# untitled.net
KiCad netlist of a schematic drawn in EAGLE
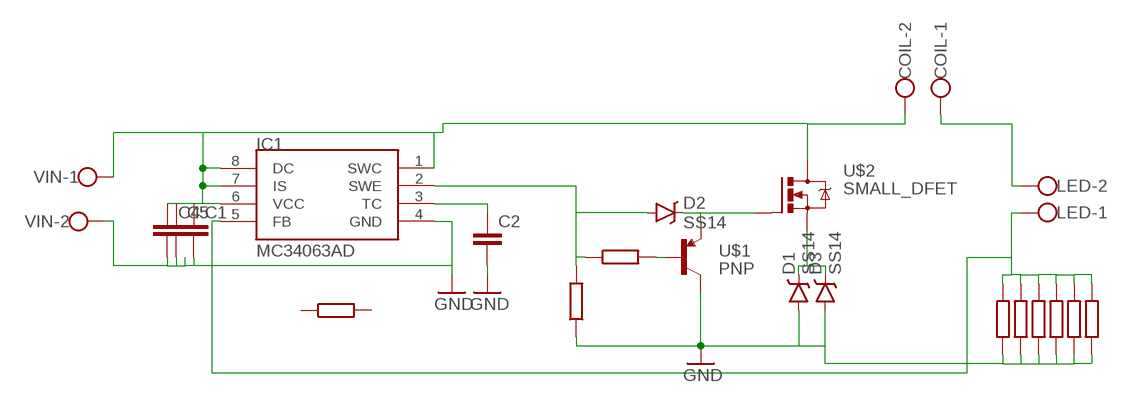
[diagram p0: schematic, sheet 1]

(export (version "E")
  (design (tool "Eeschema 10.0.6"))
  (components
    (comp (ref "C1")
      (value "CC0805")
      (footprint "eagle-import:C0805")
      (libsource (lib "eagle-import") (part "CC0805"))
    )
    (comp (ref "C2")
      (value "CC0603")
      (footprint "eagle-import:C0603")
      (libsource (lib "eagle-import") (part "CC0603"))
    )
    (comp (ref "C4")
      (value "CC0805")
      (footprint "eagle-import:C0805")
      (libsource (lib "eagle-import") (part "CC0805"))
    )
    (comp (ref "C5")
      (value "CC0805")
      (footprint "eagle-import:C0805")
      (libsource (lib "eagle-import") (part "CC0805"))
    )
    (comp (ref "COIL")
      (value "W237-102")
      (footprint "eagle-import:W237-102")
      (fields (field (name "MPN") "237-102"))
      (libsource (lib "eagle-import") (part "W237-102"))
    )
    (comp (ref "D1")
      (value "SS14")
      (footprint "eagle-import:SMA-DIODE")
      (libsource (lib "eagle-import") (part "SS14"))
    )
    (comp (ref "D2")
      (value "SS14")
      (footprint "eagle-import:SMA-DIODE")
      (libsource (lib "eagle-import") (part "SS14"))
    )
    (comp (ref "D3")
      (value "SS14")
      (footprint "eagle-import:SMA-DIODE")
      (libsource (lib "eagle-import") (part "SS14"))
    )
    (comp (ref "IC1")
      (value "MC34063AD")
      (footprint "eagle-import:SOIC8")
      (libsource (lib "eagle-import") (part "MC34063AD"))
    )
    (comp (ref "LED")
      (value "W237-102")
      (footprint "eagle-import:W237-102")
      (fields (field (name "MPN") "237-102"))
      (libsource (lib "eagle-import") (part "W237-102"))
    )
    (comp (ref "R1")
      (value "R1206")
      (footprint "eagle-import:R1206")
      (libsource (lib "eagle-import") (part "R1206"))
    )
    (comp (ref "R3")
      (value "R0805")
      (footprint "eagle-import:R0805")
      (libsource (lib "eagle-import") (part "R0805"))
    )
    (comp (ref "R4")
      (value "R0805")
      (footprint "eagle-import:R0805")
      (libsource (lib "eagle-import") (part "R0805"))
    )
    (comp (ref "R5")
      (value "R0805")
      (footprint "eagle-import:R0805")
      (libsource (lib "eagle-import") (part "R0805"))
    )
    (comp (ref "R6")
      (value "R0805")
      (footprint "eagle-import:R0805")
      (libsource (lib "eagle-import") (part "R0805"))
    )
    (comp (ref "R7")
      (value "R0805")
      (footprint "eagle-import:R0805")
      (libsource (lib "eagle-import") (part "R0805"))
    )
    (comp (ref "R8")
      (value "R0805")
      (footprint "eagle-import:R0805")
      (libsource (lib "eagle-import") (part "R0805"))
    )
    (comp (ref "R9")
      (value "R0805")
      (footprint "eagle-import:R0805")
      (libsource (lib "eagle-import") (part "R0805"))
    )
    (comp (ref "R10")
      (value "R0805")
      (footprint "eagle-import:R0805")
      (libsource (lib "eagle-import") (part "R0805"))
    )
    (comp (ref "U$1")
      (value "PNP")
      (footprint "eagle-import:SOT23")
      (libsource (lib "eagle-import") (part "PNP"))
    )
    (comp (ref "U$2")
      (value "SMALL_DFET")
      (footprint "eagle-import:SMALL_DIRFET")
      (libsource (lib "eagle-import") (part "SMALL_DFET"))
    )
    (comp (ref "VIN")
      (value "W237-102")
      (footprint "eagle-import:W237-102")
      (fields (field (name "MPN") "237-102"))
      (libsource (lib "eagle-import") (part "W237-102"))
    )
  )
  (nets
    (net (code "1") (name "GND") (class "Default")
      (node (ref "C1") (pin "2") (pinfunction "2_2") (pintype "passive"))
      (node (ref "C2") (pin "2") (pinfunction "2_2") (pintype "passive"))
      (node (ref "C4") (pin "2") (pinfunction "2_2") (pintype "passive"))
      (node (ref "C5") (pin "2") (pinfunction "2_2") (pintype "passive"))
      (node (ref "D1") (pin "A") (pinfunction "A_A") (pintype "passive"))
      (node (ref "D3") (pin "A") (pinfunction "A_A") (pintype "passive"))
      (node (ref "IC1") (pin "4") (pinfunction "GND_4") (pintype "passive"))
      (node (ref "R10") (pin "1") (pinfunction "1_1") (pintype "passive"))
      (node (ref "R4") (pin "1") (pinfunction "1_1") (pintype "passive"))
      (node (ref "R5") (pin "1") (pinfunction "1_1") (pintype "passive"))
      (node (ref "R6") (pin "1") (pinfunction "1_1") (pintype "passive"))
      (node (ref "R7") (pin "1") (pinfunction "1_1") (pintype "passive"))
      (node (ref "R8") (pin "1") (pinfunction "1_1") (pintype "passive"))
      (node (ref "R9") (pin "1") (pinfunction "1_1") (pintype "passive"))
      (node (ref "U$1") (pin "3") (pinfunction "C_3") (pintype "passive"))
      (node (ref "VIN") (pin "2") (pinfunction "KL_2") (pintype "passive"))
    )
    (net (code "2") (name "Net-(COILA-KL)") (class "Default")
      (node (ref "COIL") (pin "1") (pinfunction "KL_1") (pintype "passive"))
      (node (ref "LED") (pin "2") (pinfunction "KL_2") (pintype "passive"))
    )
    (net (code "3") (name "Net-(COILB-KL)") (class "Default")
      (node (ref "C1") (pin "1") (pinfunction "1_1") (pintype "passive"))
      (node (ref "C4") (pin "1") (pinfunction "1_1") (pintype "passive"))
      (node (ref "C5") (pin "1") (pinfunction "1_1") (pintype "passive"))
      (node (ref "COIL") (pin "2") (pinfunction "KL_2") (pintype "passive"))
      (node (ref "IC1") (pin "1") (pinfunction "SWC_1") (pintype "passive"))
      (node (ref "IC1") (pin "6") (pinfunction "VCC_6") (pintype "passive"))
      (node (ref "IC1") (pin "7") (pinfunction "IS_7") (pintype "passive"))
      (node (ref "IC1") (pin "8") (pinfunction "DC_8") (pintype "passive"))
      (node (ref "U$2") (pin "D") (pinfunction "D_D") (pintype "passive"))
      (node (ref "U$2") (pin "D`") (pinfunction "D_D`") (pintype "passive"))
      (node (ref "VIN") (pin "1") (pinfunction "KL_1") (pintype "passive"))
    )
    (net (code "4") (name "Net-(D1-PadC)") (class "Default")
      (node (ref "D1") (pin "C") (pinfunction "C_C") (pintype "passive"))
      (node (ref "D3") (pin "C") (pinfunction "C_C") (pintype "passive"))
      (node (ref "U$2") (pin "S") (pinfunction "S_S") (pintype "passive"))
    )
    (net (code "5") (name "Net-(IC1-FB)") (class "Default")
      (node (ref "IC1") (pin "5") (pinfunction "FB_5") (pintype "passive"))
      (node (ref "LED") (pin "1") (pinfunction "KL_1") (pintype "passive"))
      (node (ref "R10") (pin "2") (pinfunction "2_2") (pintype "passive"))
      (node (ref "R5") (pin "2") (pinfunction "2_2") (pintype "passive"))
      (node (ref "R6") (pin "2") (pinfunction "2_2") (pintype "passive"))
      (node (ref "R7") (pin "2") (pinfunction "2_2") (pintype "passive"))
      (node (ref "R8") (pin "2") (pinfunction "2_2") (pintype "passive"))
      (node (ref "R9") (pin "2") (pinfunction "2_2") (pintype "passive"))
    )
    (net (code "6") (name "Net-(IC1-SWE)") (class "Default")
      (node (ref "D2") (pin "A") (pinfunction "A_A") (pintype "passive"))
      (node (ref "IC1") (pin "2") (pinfunction "SWE_2") (pintype "passive"))
      (node (ref "R3") (pin "1") (pinfunction "1_1") (pintype "passive"))
      (node (ref "R4") (pin "2") (pinfunction "2_2") (pintype "passive"))
    )
    (net (code "7") (name "Net-(IC1-TC)") (class "Default")
      (node (ref "C2") (pin "1") (pinfunction "1_1") (pintype "passive"))
      (node (ref "IC1") (pin "3") (pinfunction "TC_3") (pintype "passive"))
    )
    (net (code "8") (name "Net-(U$1-B)") (class "Default")
      (node (ref "R3") (pin "2") (pinfunction "2_2") (pintype "passive"))
      (node (ref "U$1") (pin "1") (pinfunction "B_1") (pintype "passive"))
    )
    (net (code "9") (name "Net-(U$1-E)") (class "Default")
      (node (ref "D2") (pin "C") (pinfunction "C_C") (pintype "passive"))
      (node (ref "U$1") (pin "2") (pinfunction "E_2") (pintype "passive"))
      (node (ref "U$2") (pin "G") (pinfunction "G_G") (pintype "passive"))
    )
    (net (code "10") (name "unconnected-(R1-Pad1)") (class "Default")
      (node (ref "R1") (pin "1") (pinfunction "1_1") (pintype "passive"))
    )
    (net (code "11") (name "unconnected-(R1-Pad2)") (class "Default")
      (node (ref "R1") (pin "2") (pinfunction "2_2") (pintype "passive"))
    )
  )
)
